# TOP.net
KiCad netlist of a schematic drawn in Altium Designer
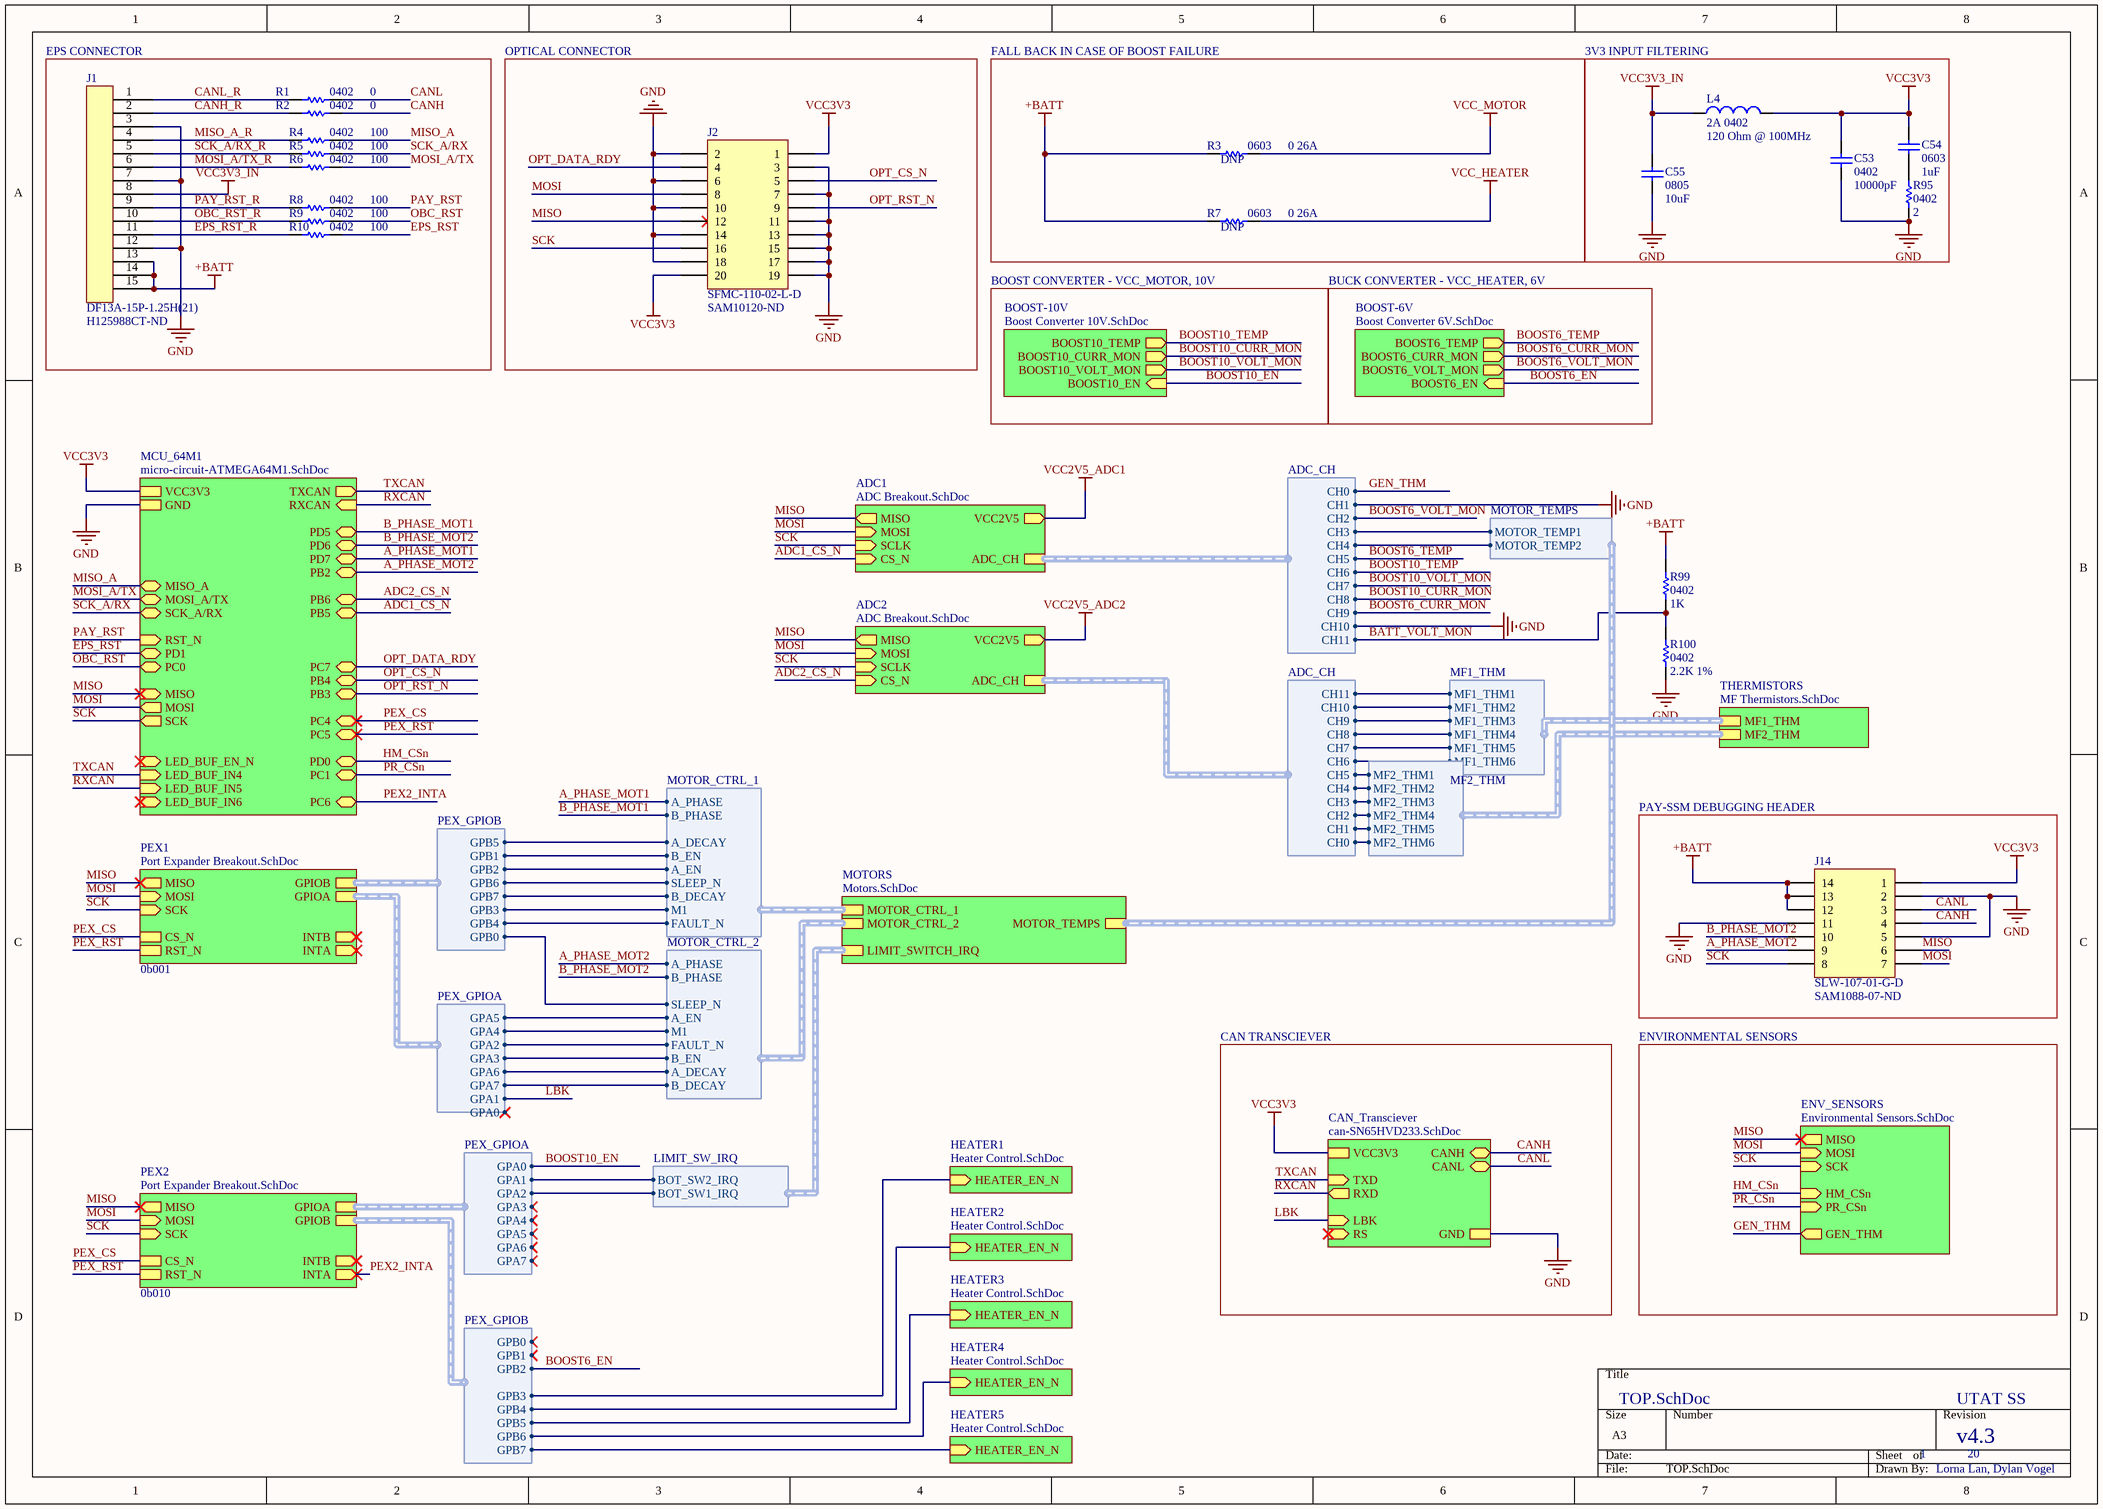
[diagram p0: TOP.SchDoc]

(export (version "E")
  (design (tool "Eeschema 10.0.6"))
  (components
    (comp (ref "C53")
      (value "0402")
      (footprint "CAP0402R")
      (description "Capacitor")
      (fields (field (name "ALTIUM_VALUE") "10000pF") (field (name "PUBLISHER") "Altium Limited"))
      (libsource (lib "Miscellaneous Devices") (part "Cap"))
    )
    (comp (ref "C54")
      (value "0603")
      (footprint "CAP0603R")
      (description "0603 capacitor")
      (fields
        (field (name "ALTIUM_VALUE") "1uF")
        (field (name "MANUFACTURER") "KEMET")
        (field (name "MANUFACTURER PART NUMBER") "C0603C105K4RACAUTO")
      )
      (libsource (lib "heron-general") (part "CAP0603"))
    )
    (comp (ref "C55")
      (value "0805")
      (footprint "CAP0805R")
      (description "0805 capacitor")
      (fields
        (field (name "ALTIUM_VALUE") "10uF")
        (field (name "MANUFACTURER") "Murata")
        (field (name "MANUFACTURER PART NUMBER") "GCM21BR70J106KE22K")
      )
      (libsource (lib "heron-general") (part "CAP0805"))
    )
    (comp (ref "J1")
      (value "DF13A-15P-1.25H(21)")
      (footprint "DF13A-15P-1.25H(21)")
      (description "15 pos DF13 right angle surface mount connector")
      (fields (field (name "SUPPLIER PART NUMBER 1") "H125988CT-ND"))
      (libsource (lib "heron-general") (part "DF13A-15P-1.25H(21)"))
    )
    (comp (ref "J2")
      (value "SFMC-110-02-L-D")
      (footprint "TFM-110-02-L-D:TFM-110-02-L-D")
      (description "20 pos 50mil pitch low profile SMD connector")
      (fields (field (name "SUPPLIER PART NUMBER 1") "SAM10120-ND"))
      (libsource (lib "TFM-110-02-L-D") (part "SFMC-110-02-L-D"))
    )
    (comp (ref "J14")
      (value "SLW-107-01-G-D")
      (footprint "SLW-107-01-X-D")
      (description "14 pos 100 mil pitch low profile header")
      (fields (field (name "SUPPLIER PART NUMBER 1") "SAM1088-07-ND"))
      (libsource (lib "heron-general") (part "SLW-107-01-G-D"))
    )
    (comp (ref "L4")
      (value "2A 0402")
      (footprint "RES0402R")
      (description "Inductor")
      (fields
        (field (name "ALTIUM_VALUE") "120 Ohm @ 100MHz")
        (field (name "MANUFACTURER") "Murata")
        (field (name "MANUFACTURER PART NUMBER") "BLM15PX121SZ1D")
        (field (name "PUBLISHER") "Altium Limited")
      )
      (libsource (lib "Miscellaneous Devices") (part "Inductor"))
    )
    (comp (ref "R1")
      (value "0402")
      (footprint "RES0402R")
      (description "0402 resistor")
      (fields
        (field (name "ALTIUM_VALUE") "0")
        (field (name "MANUFACTURER") "Panasonic")
        (field (name "MANUFACTURER PART NUMBER") "ERJ-2GE0R00X")
      )
      (libsource (lib "heron-general") (part "RES0402"))
    )
    (comp (ref "R2")
      (value "0402")
      (footprint "RES0402R")
      (description "0402 resistor")
      (fields
        (field (name "ALTIUM_VALUE") "0")
        (field (name "MANUFACTURER") "Panasonic")
        (field (name "MANUFACTURER PART NUMBER") "ERJ-2GE0R00X")
      )
      (libsource (lib "heron-general") (part "RES0402"))
    )
    (comp (ref "R3")
      (value "0603")
      (footprint "RES0603R")
      (description "0603 resistor")
      (fields (field (name "ALTIUM_VALUE") "0 26A"))
      (libsource (lib "heron-general") (part "RES0603"))
    )
    (comp (ref "R4")
      (value "0402")
      (footprint "RES0402R")
      (description "0402 resistor")
      (fields (field (name "ALTIUM_VALUE") "100"))
      (libsource (lib "heron-general") (part "RES0402"))
    )
    (comp (ref "R5")
      (value "0402")
      (footprint "RES0402R")
      (description "0402 resistor")
      (fields (field (name "ALTIUM_VALUE") "100"))
      (libsource (lib "heron-general") (part "RES0402"))
    )
    (comp (ref "R6")
      (value "0402")
      (footprint "RES0402R")
      (description "0402 resistor")
      (fields (field (name "ALTIUM_VALUE") "100"))
      (libsource (lib "heron-general") (part "RES0402"))
    )
    (comp (ref "R7")
      (value "0603")
      (footprint "RES0603R")
      (description "0603 resistor")
      (fields (field (name "ALTIUM_VALUE") "0 26A"))
      (libsource (lib "heron-general") (part "RES0603"))
    )
    (comp (ref "R8")
      (value "0402")
      (footprint "RES0402R")
      (description "0402 resistor")
      (fields (field (name "ALTIUM_VALUE") "100"))
      (libsource (lib "heron-general") (part "RES0402"))
    )
    (comp (ref "R9")
      (value "0402")
      (footprint "RES0402R")
      (description "0402 resistor")
      (fields (field (name "ALTIUM_VALUE") "100"))
      (libsource (lib "heron-general") (part "RES0402"))
    )
    (comp (ref "R10")
      (value "0402")
      (footprint "RES0402R")
      (description "0402 resistor")
      (fields (field (name "ALTIUM_VALUE") "100"))
      (libsource (lib "heron-general") (part "RES0402"))
    )
    (comp (ref "R95")
      (value "0402")
      (footprint "RES0402R")
      (description "Resistor")
      (fields (field (name "ALTIUM_VALUE") "2") (field (name "PUBLISHER") "Altium Limited"))
      (libsource (lib "Miscellaneous Devices") (part "Res1"))
    )
    (comp (ref "R99")
      (value "0402")
      (footprint "RES0402R")
      (description "0402 resistor")
      (fields (field (name "ALTIUM_VALUE") "1K"))
      (libsource (lib "RES0402") (part "RES0402"))
    )
    (comp (ref "R100")
      (value "0402")
      (footprint "RES0402R")
      (description "0402 resistor")
      (fields (field (name "ALTIUM_VALUE") "2.2K 1%"))
      (libsource (lib "heron-general") (part "RES0402"))
    )
  )
  (nets
    (net (code "10") (name "+BATT") (class "Default")
      (node (ref "J1") (pin "13") (pintype "passive"))
      (node (ref "J1") (pin "14") (pintype "passive"))
      (node (ref "J1") (pin "15") (pintype "passive"))
      (node (ref "J14") (pin "2") (pinfunction "14_2") (pintype "passive"))
      (node (ref "J14") (pin "4") (pinfunction "13_4") (pintype "passive"))
      (node (ref "J14") (pin "6") (pinfunction "12_6") (pintype "passive"))
      (node (ref "R3") (pin "1") (pinfunction "1_1") (pintype "passive"))
      (node (ref "R7") (pin "1") (pinfunction "1_1") (pintype "passive"))
      (node (ref "R99") (pin "2") (pinfunction "2_2") (pintype "passive"))
    )
    (net (code "14") (name "/A_PHASE_MOT2") (class "Default")
      (node (ref "J14") (pin "12") (pinfunction "9_12") (pintype "passive"))
    )
    (net (code "15") (name "/BATT_VOLT_MON") (class "Default")
      (node (ref "R100") (pin "2") (pinfunction "2_2") (pintype "passive"))
      (node (ref "R99") (pin "1") (pinfunction "1_1") (pintype "passive"))
    )
    (net (code "25") (name "/B_PHASE_MOT2") (class "Default")
      (node (ref "J14") (pin "10") (pinfunction "10_10") (pintype "passive"))
    )
    (net (code "26") (name "/CANH") (class "Default")
      (node (ref "J14") (pin "7") (pinfunction "4_7") (pintype "passive"))
      (node (ref "R2") (pin "2") (pinfunction "2_2") (pintype "passive"))
    )
    (net (code "27") (name "/CANH_R") (class "Default")
      (node (ref "J1") (pin "2") (pintype "passive"))
      (node (ref "R2") (pin "1") (pinfunction "1_1") (pintype "passive"))
    )
    (net (code "28") (name "/CANL") (class "Default")
      (node (ref "J14") (pin "5") (pinfunction "3_5") (pintype "passive"))
      (node (ref "R1") (pin "2") (pinfunction "2_2") (pintype "passive"))
    )
    (net (code "29") (name "/CANL_R") (class "Default")
      (node (ref "J1") (pin "1") (pintype "passive"))
      (node (ref "R1") (pin "1") (pinfunction "1_1") (pintype "passive"))
    )
    (net (code "30") (name "/EPS_RST") (class "Default")
      (node (ref "R10") (pin "2") (pinfunction "2_2") (pintype "passive"))
    )
    (net (code "31") (name "/EPS_RST_R") (class "Default")
      (node (ref "J1") (pin "11") (pintype "passive"))
      (node (ref "R10") (pin "1") (pinfunction "1_1") (pintype "passive"))
    )
    (net (code "45") (name "/MISO") (class "Default")
      (node (ref "J14") (pin "11") (pinfunction "6_11") (pintype "passive"))
      (node (ref "J2") (pin "12") (pinfunction "12_12") (pintype "passive"))
    )
    (net (code "46") (name "/MISO_A") (class "Default")
      (node (ref "R4") (pin "2") (pinfunction "2_2") (pintype "passive"))
    )
    (net (code "47") (name "/MISO_A_R") (class "Default")
      (node (ref "J1") (pin "4") (pintype "passive"))
      (node (ref "R4") (pin "1") (pinfunction "1_1") (pintype "passive"))
    )
    (net (code "48") (name "/MOSI") (class "Default")
      (node (ref "J14") (pin "13") (pinfunction "7_13") (pintype "passive"))
      (node (ref "J2") (pin "8") (pinfunction "8_8") (pintype "passive"))
    )
    (net (code "49") (name "/MOSI_A{slash}TX") (class "Default")
      (node (ref "R6") (pin "2") (pinfunction "2_2") (pintype "passive"))
    )
    (net (code "50") (name "/MOSI_A{slash}TX_R") (class "Default")
      (node (ref "J1") (pin "6") (pintype "passive"))
      (node (ref "R6") (pin "1") (pinfunction "1_1") (pintype "passive"))
    )
    (net (code "51") (name "/OBC_RST") (class "Default")
      (node (ref "R9") (pin "2") (pinfunction "2_2") (pintype "passive"))
    )
    (net (code "52") (name "/OBC_RST_R") (class "Default")
      (node (ref "J1") (pin "10") (pintype "passive"))
      (node (ref "R9") (pin "1") (pinfunction "1_1") (pintype "passive"))
    )
    (net (code "53") (name "/OPT_CS_N") (class "Default")
      (node (ref "J2") (pin "5") (pinfunction "5_5") (pintype "passive"))
    )
    (net (code "54") (name "/OPT_DATA_RDY") (class "Default")
      (node (ref "J2") (pin "4") (pinfunction "4_4") (pintype "passive"))
    )
    (net (code "55") (name "/OPT_RST_N") (class "Default")
      (node (ref "J2") (pin "9") (pinfunction "9_9") (pintype "passive"))
    )
    (net (code "56") (name "/PAY_RST") (class "Default")
      (node (ref "R8") (pin "2") (pinfunction "2_2") (pintype "passive"))
    )
    (net (code "57") (name "/PAY_RST_R") (class "Default")
      (node (ref "J1") (pin "9") (pintype "passive"))
      (node (ref "R8") (pin "1") (pinfunction "1_1") (pintype "passive"))
    )
    (net (code "64") (name "/SCK") (class "Default")
      (node (ref "J14") (pin "14") (pinfunction "8_14") (pintype "passive"))
      (node (ref "J2") (pin "16") (pinfunction "16_16") (pintype "passive"))
    )
    (net (code "65") (name "/SCK_A{slash}RX") (class "Default")
      (node (ref "R5") (pin "2") (pinfunction "2_2") (pintype "passive"))
    )
    (net (code "66") (name "/SCK_A{slash}RX_R") (class "Default")
      (node (ref "J1") (pin "5") (pintype "passive"))
      (node (ref "R5") (pin "1") (pinfunction "1_1") (pintype "passive"))
    )
    (net (code "77") (name "GND") (class "Default")
      (node (ref "C53") (pin "1") (pinfunction "1_1") (pintype "passive"))
      (node (ref "C55") (pin "1") (pinfunction "1_1") (pintype "passive"))
      (node (ref "J1") (pin "12") (pintype "passive"))
      (node (ref "J1") (pin "3") (pintype "passive"))
      (node (ref "J1") (pin "7") (pintype "passive"))
      (node (ref "J14") (pin "3") (pinfunction "2_3") (pintype "passive"))
      (node (ref "J14") (pin "8") (pinfunction "11_8") (pintype "passive"))
      (node (ref "J14") (pin "9") (pinfunction "5_9") (pintype "passive"))
      (node (ref "J2") (pin "10") (pinfunction "10_10") (pintype "passive"))
      (node (ref "J2") (pin "11") (pinfunction "11_11") (pintype "passive"))
      (node (ref "J2") (pin "13") (pinfunction "13_13") (pintype "passive"))
      (node (ref "J2") (pin "14") (pinfunction "14_14") (pintype "passive"))
      (node (ref "J2") (pin "15") (pinfunction "15_15") (pintype "passive"))
      (node (ref "J2") (pin "17") (pinfunction "17_17") (pintype "passive"))
      (node (ref "J2") (pin "18") (pinfunction "18_18") (pintype "passive"))
      (node (ref "J2") (pin "19") (pinfunction "19_19") (pintype "passive"))
      (node (ref "J2") (pin "2") (pinfunction "2_2") (pintype "passive"))
      (node (ref "J2") (pin "3") (pinfunction "3_3") (pintype "passive"))
      (node (ref "J2") (pin "6") (pinfunction "6_6") (pintype "passive"))
      (node (ref "J2") (pin "7") (pinfunction "7_7") (pintype "passive"))
      (node (ref "R100") (pin "1") (pinfunction "1_1") (pintype "passive"))
      (node (ref "R95") (pin "1") (pinfunction "1_1") (pintype "passive"))
    )
    (net (code "78") (name "Net-(C54-Pad1)") (class "Default")
      (node (ref "C54") (pin "1") (pinfunction "1_1") (pintype "passive"))
      (node (ref "R95") (pin "2") (pinfunction "2_2") (pintype "passive"))
    )
    (net (code "81") (name "VCC3V3") (class "Default")
      (node (ref "C53") (pin "2") (pinfunction "2_2") (pintype "passive"))
      (node (ref "C54") (pin "2") (pinfunction "2_2") (pintype "passive"))
      (node (ref "J14") (pin "1") (pinfunction "1_1") (pintype "passive"))
      (node (ref "J2") (pin "1") (pinfunction "1_1") (pintype "passive"))
      (node (ref "J2") (pin "20") (pinfunction "20_20") (pintype "passive"))
      (node (ref "L4") (pin "2") (pinfunction "2_2") (pintype "passive"))
    )
    (net (code "82") (name "VCC3V3_IN") (class "Default")
      (node (ref "C55") (pin "2") (pinfunction "2_2") (pintype "passive"))
      (node (ref "J1") (pin "8") (pintype "passive"))
      (node (ref "L4") (pin "1") (pinfunction "1_1") (pintype "passive"))
    )
    (net (code "83") (name "VCC_HEATER") (class "Default")
      (node (ref "R7") (pin "2") (pinfunction "2_2") (pintype "passive"))
    )
    (net (code "84") (name "VCC_MOTOR") (class "Default")
      (node (ref "R3") (pin "2") (pinfunction "2_2") (pintype "passive"))
    )
  )
)
